# RPi_board_0_0_1.net
KiCad netlist of a schematic drawn in EAGLE
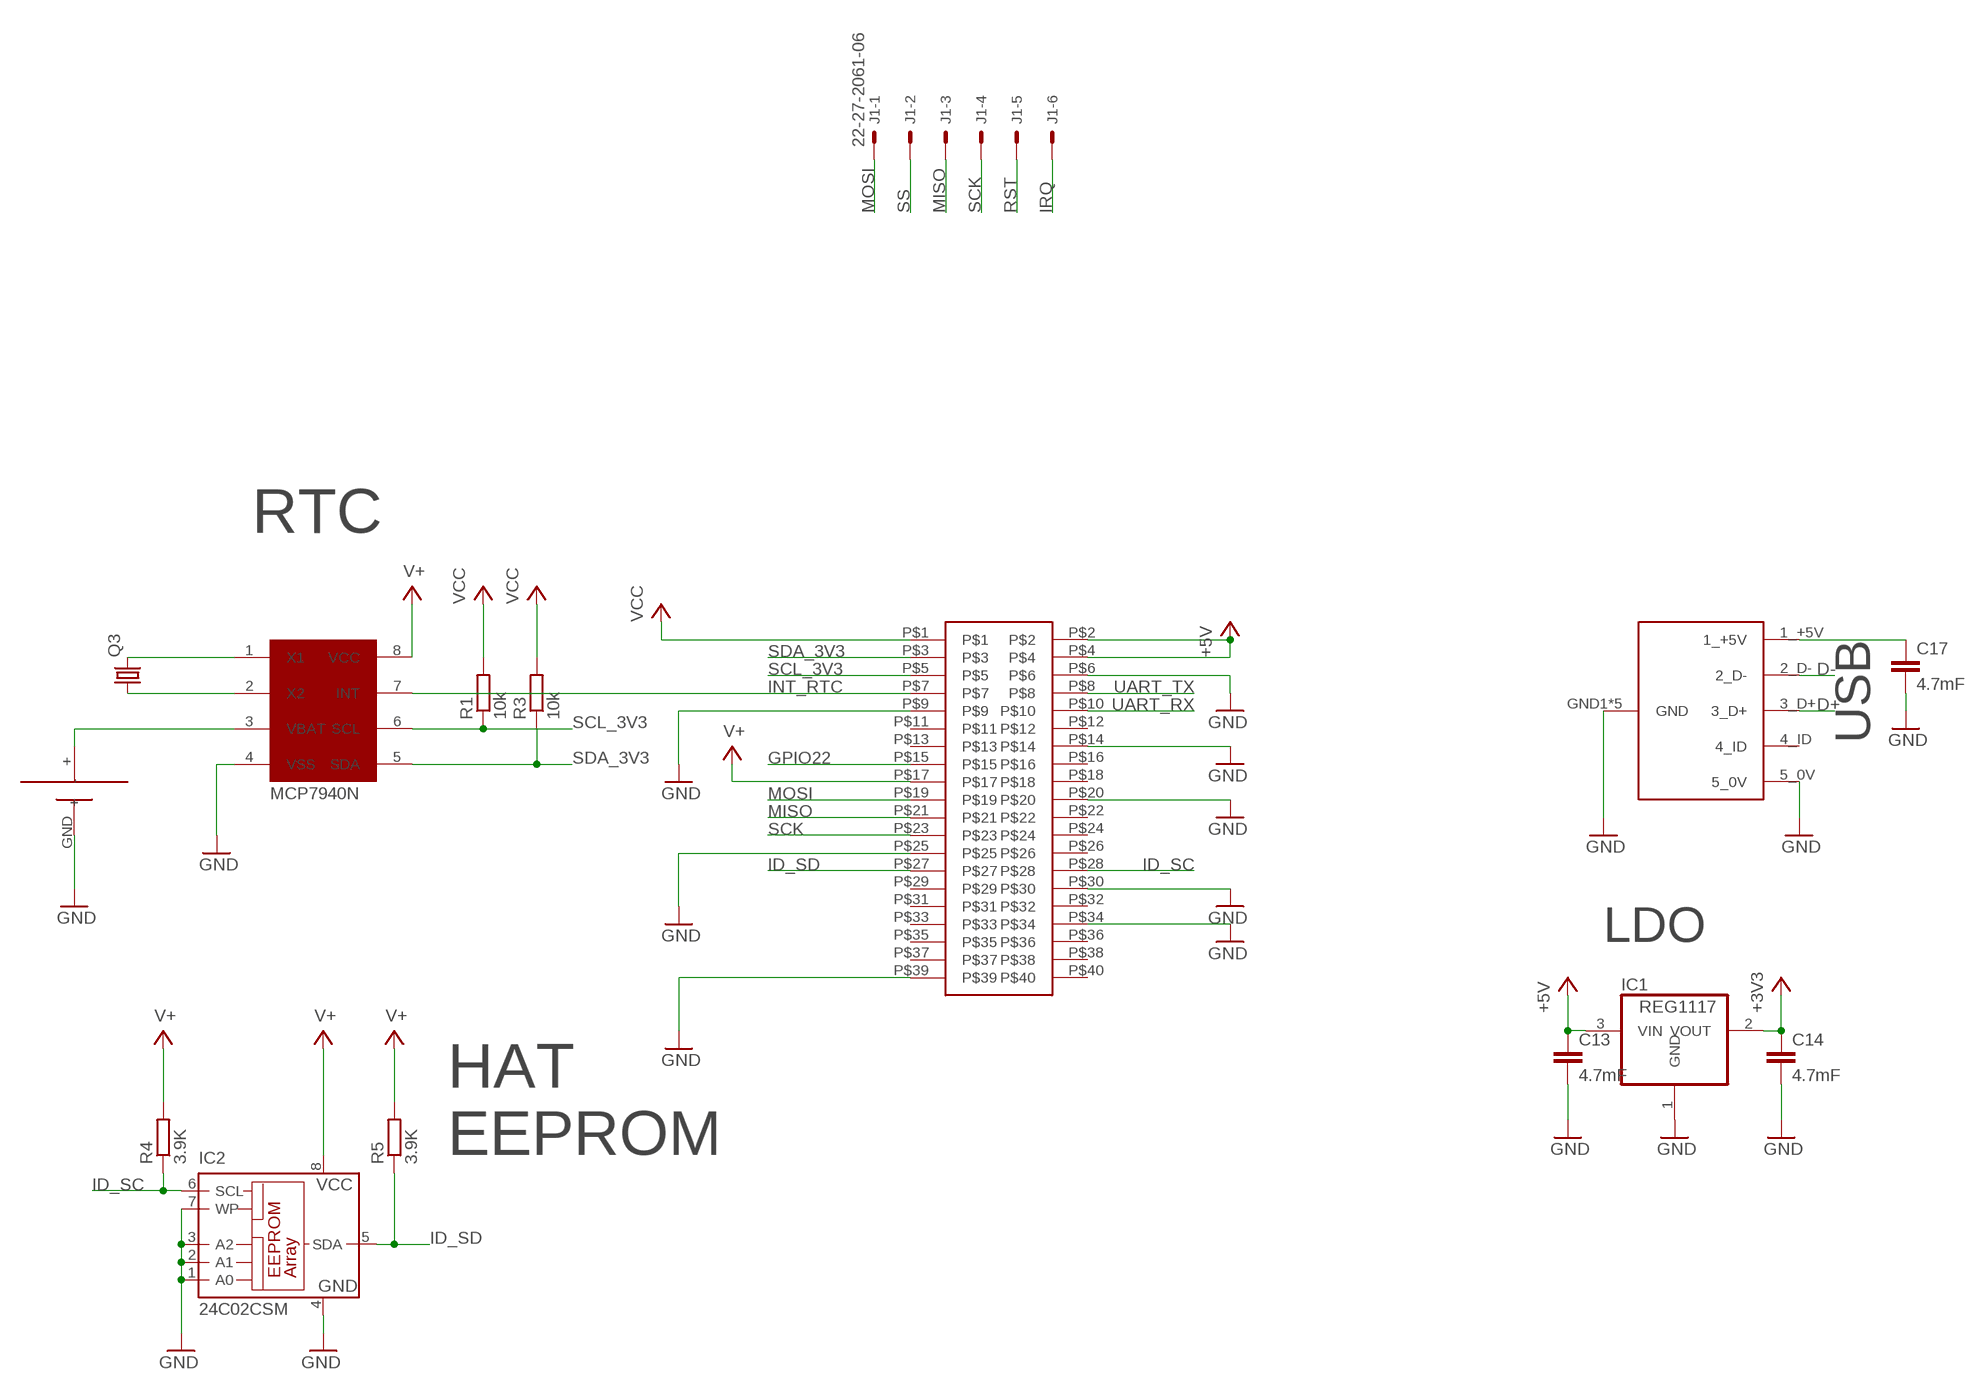
[diagram p0: schematic, sheet 1]

(export (version "E")
  (design (tool "Eeschema 10.0.6"))
  (components
    (comp (ref "C13")
      (value "4.7mF")
      (footprint "eagle-import:C0603")
      (libsource (lib "eagle-import") (part "C-EUC0603"))
    )
    (comp (ref "C14")
      (value "4.7mF")
      (footprint "eagle-import:C0603")
      (libsource (lib "eagle-import") (part "C-EUC0603"))
    )
    (comp (ref "C17")
      (value "4.7mF")
      (footprint "eagle-import:C0603")
      (libsource (lib "eagle-import") (part "C-EUC0603"))
    )
    (comp (ref "IC1")
      (value "REG1117")
      (footprint "eagle-import:SOT223")
      (libsource (lib "eagle-import") (part "REG1117"))
    )
    (comp (ref "IC2")
      (value "24C02CSM")
      (footprint "eagle-import:SO-08M")
      (fields (field (name "MF") "MICROCHIP") (field (name "MPN") "24C02C-I/SN"))
      (libsource (lib "eagle-import") (part "24CSM02C"))
    )
    (comp (ref "J1")
      (value "22-27-2061-06")
      (footprint "eagle-import:6410-06")
      (libsource (lib "eagle-import") (part "22-?-0627-2061"))
    )
    (comp (ref "Q3")
      (value "CRYSTALMM20SS")
      (footprint "eagle-import:MM20SS")
      (libsource (lib "eagle-import") (part "CRYSTALMM20SS"))
    )
    (comp (ref "R1")
      (value "10k")
      (footprint "eagle-import:R0603")
      (libsource (lib "eagle-import") (part "R-EU_R0603"))
    )
    (comp (ref "R3")
      (value "10k")
      (footprint "eagle-import:R0603")
      (libsource (lib "eagle-import") (part "R-EU_R0603"))
    )
    (comp (ref "R4")
      (value "3.9K")
      (footprint "eagle-import:R0603")
      (libsource (lib "eagle-import") (part "R-EU_R0603"))
    )
    (comp (ref "R5")
      (value "3.9K")
      (footprint "eagle-import:R0603")
      (libsource (lib "eagle-import") (part "R-EU_R0603"))
    )
    (comp (ref "U$4")
      (value "CR1216")
      (footprint "eagle-import:CR1216")
      (libsource (lib "eagle-import") (part "CR1216"))
    )
    (comp (ref "U$5")
      (value "MCP7940N")
      (footprint "eagle-import:SO08")
      (libsource (lib "eagle-import") (part "MCP7940N"))
    )
    (comp (ref "U$9")
      (value "MICRO_USB")
      (footprint "eagle-import:MICRO_USB")
      (libsource (lib "eagle-import") (part "MICRO_USB"))
    )
    (comp (ref "U$11")
      (value "HEADER")
      (footprint "eagle-import:20X2")
      (libsource (lib "eagle-import") (part "HEADER"))
    )
  )
  (nets
    (net (code "1") (name "+3V3") (class "Default")
      (node (ref "C14") (pin "1") (pinfunction "1_1") (pintype "passive"))
      (node (ref "IC1") (pin "2") (pinfunction "VOUT_2") (pintype "output"))
    )
    (net (code "2") (name "+5V") (class "Default")
      (node (ref "C13") (pin "1") (pinfunction "1_1") (pintype "passive"))
      (node (ref "IC1") (pin "3") (pinfunction "VIN_3") (pintype "input"))
      (node (ref "U$11") (pin "P$2") (pinfunction "P$2_P$2") (pintype "bidirectional"))
      (node (ref "U$11") (pin "P$4") (pinfunction "P$4_P$4") (pintype "bidirectional"))
    )
    (net (code "3") (name "/D+") (class "Default")
      (node (ref "U$9") (pin "3_D+") (pinfunction "3_D+_3_D+") (pintype "bidirectional"))
    )
    (net (code "4") (name "/D-") (class "Default")
      (node (ref "U$9") (pin "2_D-") (pinfunction "2_D-_2_D-") (pintype "bidirectional"))
    )
    (net (code "5") (name "/GPIO22") (class "Default")
      (node (ref "U$11") (pin "P$15") (pinfunction "P$15_P$15") (pintype "bidirectional"))
    )
    (net (code "6") (name "/ID_SC") (class "Default")
      (node (ref "IC2") (pin "6") (pinfunction "SCL_6") (pintype "input"))
      (node (ref "R4") (pin "1") (pinfunction "1_1") (pintype "passive"))
      (node (ref "U$11") (pin "P$28") (pinfunction "P$28_P$28") (pintype "bidirectional"))
    )
    (net (code "7") (name "/ID_SD") (class "Default")
      (node (ref "IC2") (pin "5") (pinfunction "SDA_5") (pintype "bidirectional"))
      (node (ref "R5") (pin "1") (pinfunction "1_1") (pintype "passive"))
      (node (ref "U$11") (pin "P$27") (pinfunction "P$27_P$27") (pintype "bidirectional"))
    )
    (net (code "8") (name "/INT_RTC") (class "Default")
      (node (ref "U$11") (pin "P$7") (pinfunction "P$7_P$7") (pintype "bidirectional"))
      (node (ref "U$5") (pin "7") (pinfunction "INT_7") (pintype "bidirectional"))
    )
    (net (code "9") (name "/IRQ") (class "Default")
      (node (ref "J1") (pin "6") (pinfunction "S_6") (pintype "passive"))
    )
    (net (code "10") (name "/MISO") (class "Default")
      (node (ref "J1") (pin "3") (pinfunction "S_3") (pintype "passive"))
      (node (ref "U$11") (pin "P$21") (pinfunction "P$21_P$21") (pintype "bidirectional"))
    )
    (net (code "11") (name "/MOSI") (class "Default")
      (node (ref "J1") (pin "1") (pinfunction "S_1") (pintype "passive"))
      (node (ref "U$11") (pin "P$19") (pinfunction "P$19_P$19") (pintype "bidirectional"))
    )
    (net (code "12") (name "/RST") (class "Default")
      (node (ref "J1") (pin "5") (pinfunction "S_5") (pintype "passive"))
    )
    (net (code "13") (name "/SCK") (class "Default")
      (node (ref "J1") (pin "4") (pinfunction "S_4") (pintype "passive"))
      (node (ref "U$11") (pin "P$23") (pinfunction "P$23_P$23") (pintype "bidirectional"))
    )
    (net (code "14") (name "/SCL_3V3") (class "Default")
      (node (ref "R1") (pin "1") (pinfunction "1_1") (pintype "passive"))
      (node (ref "U$11") (pin "P$5") (pinfunction "P$5_P$5") (pintype "bidirectional"))
      (node (ref "U$5") (pin "6") (pinfunction "SCL_6") (pintype "bidirectional"))
    )
    (net (code "15") (name "/SDA_3V3") (class "Default")
      (node (ref "R3") (pin "1") (pinfunction "1_1") (pintype "passive"))
      (node (ref "U$11") (pin "P$3") (pinfunction "P$3_P$3") (pintype "bidirectional"))
      (node (ref "U$5") (pin "5") (pinfunction "SDA_5") (pintype "bidirectional"))
    )
    (net (code "16") (name "/SS") (class "Default")
      (node (ref "J1") (pin "2") (pinfunction "S_2") (pintype "passive"))
    )
    (net (code "17") (name "/UART_RX") (class "Default")
      (node (ref "U$11") (pin "P$10") (pinfunction "P$10_P$10") (pintype "bidirectional"))
    )
    (net (code "18") (name "/UART_TX") (class "Default")
      (node (ref "U$11") (pin "P$8") (pinfunction "P$8_P$8") (pintype "bidirectional"))
    )
    (net (code "19") (name "GND") (class "Default")
      (node (ref "C13") (pin "2") (pinfunction "2_2") (pintype "passive"))
      (node (ref "C14") (pin "2") (pinfunction "2_2") (pintype "passive"))
      (node (ref "C17") (pin "2") (pinfunction "2_2") (pintype "passive"))
      (node (ref "IC1") (pin "1") (pinfunction "GND_1") (pintype "power_in"))
      (node (ref "IC2") (pin "1") (pinfunction "A0_1") (pintype "input"))
      (node (ref "IC2") (pin "2") (pinfunction "A1_2") (pintype "input"))
      (node (ref "IC2") (pin "3") (pinfunction "A2_3") (pintype "input"))
      (node (ref "IC2") (pin "4") (pinfunction "GND_4") (pintype "power_in"))
      (node (ref "IC2") (pin "7") (pinfunction "WP_7") (pintype "input"))
      (node (ref "U$11") (pin "P$14") (pinfunction "P$14_P$14") (pintype "bidirectional"))
      (node (ref "U$11") (pin "P$20") (pinfunction "P$20_P$20") (pintype "bidirectional"))
      (node (ref "U$11") (pin "P$25") (pinfunction "P$25_P$25") (pintype "bidirectional"))
      (node (ref "U$11") (pin "P$30") (pinfunction "P$30_P$30") (pintype "bidirectional"))
      (node (ref "U$11") (pin "P$34") (pinfunction "P$34_P$34") (pintype "bidirectional"))
      (node (ref "U$11") (pin "P$39") (pinfunction "P$39_P$39") (pintype "bidirectional"))
      (node (ref "U$11") (pin "P$6") (pinfunction "P$6_P$6") (pintype "bidirectional"))
      (node (ref "U$11") (pin "P$9") (pinfunction "P$9_P$9") (pintype "bidirectional"))
      (node (ref "U$4") (pin "GND") (pinfunction "-_GND") (pintype "bidirectional"))
      (node (ref "U$5") (pin "4") (pinfunction "VSS_4") (pintype "bidirectional"))
      (node (ref "U$9") (pin "5_0V") (pinfunction "5_0V_5_0V") (pintype "bidirectional"))
      (node (ref "U$9") (pin "GND1") (pinfunction "GND_GND1") (pintype "bidirectional"))
      (node (ref "U$9") (pin "GND2") (pinfunction "GND_GND2") (pintype "bidirectional"))
      (node (ref "U$9") (pin "GND5") (pinfunction "GND_GND5") (pintype "bidirectional"))
      (node (ref "U$9") (pin "P$1") (pinfunction "GND_P$1") (pintype "bidirectional"))
      (node (ref "U$9") (pin "P$7") (pinfunction "GND_P$7") (pintype "bidirectional"))
    )
    (net (code "20") (name "Net-(C17-Pad1)") (class "Default")
      (node (ref "C17") (pin "1") (pinfunction "1_1") (pintype "passive"))
      (node (ref "U$9") (pin "1_+5V") (pinfunction "1_+5V_1_+5V") (pintype "bidirectional"))
    )
    (net (code "21") (name "Net-(Q3-2)") (class "Default")
      (node (ref "Q3") (pin "4") (pinfunction "2_4") (pintype "passive"))
      (node (ref "U$5") (pin "1") (pinfunction "X1_1") (pintype "bidirectional"))
    )
    (net (code "22") (name "Net-(U$5-VBAT)") (class "Default")
      (node (ref "U$4") (pin "+") (pinfunction "+_+") (pintype "bidirectional"))
      (node (ref "U$5") (pin "3") (pinfunction "VBAT_3") (pintype "bidirectional"))
    )
    (net (code "23") (name "Net-(U$5-X2)") (class "Default")
      (node (ref "Q3") (pin "1") (pinfunction "1_1") (pintype "passive"))
      (node (ref "U$5") (pin "2") (pinfunction "X2_2") (pintype "bidirectional"))
    )
    (net (code "24") (name "V+") (class "Default")
      (node (ref "IC2") (pin "8") (pinfunction "VCC_8") (pintype "power_in"))
      (node (ref "R4") (pin "2") (pinfunction "2_2") (pintype "passive"))
      (node (ref "R5") (pin "2") (pinfunction "2_2") (pintype "passive"))
      (node (ref "U$11") (pin "P$17") (pinfunction "P$17_P$17") (pintype "bidirectional"))
      (node (ref "U$5") (pin "8") (pinfunction "VCC_8") (pintype "bidirectional"))
    )
    (net (code "25") (name "VCC") (class "Default")
      (node (ref "R1") (pin "2") (pinfunction "2_2") (pintype "passive"))
      (node (ref "R3") (pin "2") (pinfunction "2_2") (pintype "passive"))
      (node (ref "U$11") (pin "P$1") (pinfunction "P$1_P$1") (pintype "bidirectional"))
    )
    (net (code "26") (name "unconnected-(U$9-Pad4_ID)") (class "Default")
      (node (ref "U$9") (pin "4_ID") (pinfunction "4_ID_4_ID") (pintype "bidirectional"))
    )
    (net (code "27") (name "unconnected-(U$11-PadP$11)") (class "Default")
      (node (ref "U$11") (pin "P$11") (pinfunction "P$11_P$11") (pintype "bidirectional"))
    )
    (net (code "28") (name "unconnected-(U$11-PadP$12)") (class "Default")
      (node (ref "U$11") (pin "P$12") (pinfunction "P$12_P$12") (pintype "bidirectional"))
    )
    (net (code "29") (name "unconnected-(U$11-PadP$13)") (class "Default")
      (node (ref "U$11") (pin "P$13") (pinfunction "P$13_P$13") (pintype "bidirectional"))
    )
    (net (code "30") (name "unconnected-(U$11-PadP$16)") (class "Default")
      (node (ref "U$11") (pin "P$16") (pinfunction "P$16_P$16") (pintype "bidirectional"))
    )
    (net (code "31") (name "unconnected-(U$11-PadP$18)") (class "Default")
      (node (ref "U$11") (pin "P$18") (pinfunction "P$18_P$18") (pintype "bidirectional"))
    )
    (net (code "32") (name "unconnected-(U$11-PadP$22)") (class "Default")
      (node (ref "U$11") (pin "P$22") (pinfunction "P$22_P$22") (pintype "bidirectional"))
    )
    (net (code "33") (name "unconnected-(U$11-PadP$24)") (class "Default")
      (node (ref "U$11") (pin "P$24") (pinfunction "P$24_P$24") (pintype "bidirectional"))
    )
    (net (code "34") (name "unconnected-(U$11-PadP$26)") (class "Default")
      (node (ref "U$11") (pin "P$26") (pinfunction "P$26_P$26") (pintype "bidirectional"))
    )
    (net (code "35") (name "unconnected-(U$11-PadP$29)") (class "Default")
      (node (ref "U$11") (pin "P$29") (pinfunction "P$29_P$29") (pintype "bidirectional"))
    )
    (net (code "36") (name "unconnected-(U$11-PadP$31)") (class "Default")
      (node (ref "U$11") (pin "P$31") (pinfunction "P$31_P$31") (pintype "bidirectional"))
    )
    (net (code "37") (name "unconnected-(U$11-PadP$32)") (class "Default")
      (node (ref "U$11") (pin "P$32") (pinfunction "P$32_P$32") (pintype "bidirectional"))
    )
    (net (code "38") (name "unconnected-(U$11-PadP$33)") (class "Default")
      (node (ref "U$11") (pin "P$33") (pinfunction "P$33_P$33") (pintype "bidirectional"))
    )
    (net (code "39") (name "unconnected-(U$11-PadP$35)") (class "Default")
      (node (ref "U$11") (pin "P$35") (pinfunction "P$35_P$35") (pintype "bidirectional"))
    )
    (net (code "40") (name "unconnected-(U$11-PadP$36)") (class "Default")
      (node (ref "U$11") (pin "P$36") (pinfunction "P$36_P$36") (pintype "bidirectional"))
    )
    (net (code "41") (name "unconnected-(U$11-PadP$37)") (class "Default")
      (node (ref "U$11") (pin "P$37") (pinfunction "P$37_P$37") (pintype "bidirectional"))
    )
    (net (code "42") (name "unconnected-(U$11-PadP$38)") (class "Default")
      (node (ref "U$11") (pin "P$38") (pinfunction "P$38_P$38") (pintype "bidirectional"))
    )
    (net (code "43") (name "unconnected-(U$11-PadP$40)") (class "Default")
      (node (ref "U$11") (pin "P$40") (pinfunction "P$40_P$40") (pintype "bidirectional"))
    )
  )
)
